# design.net
KiCad netlist of a schematic drawn in Altium Designer
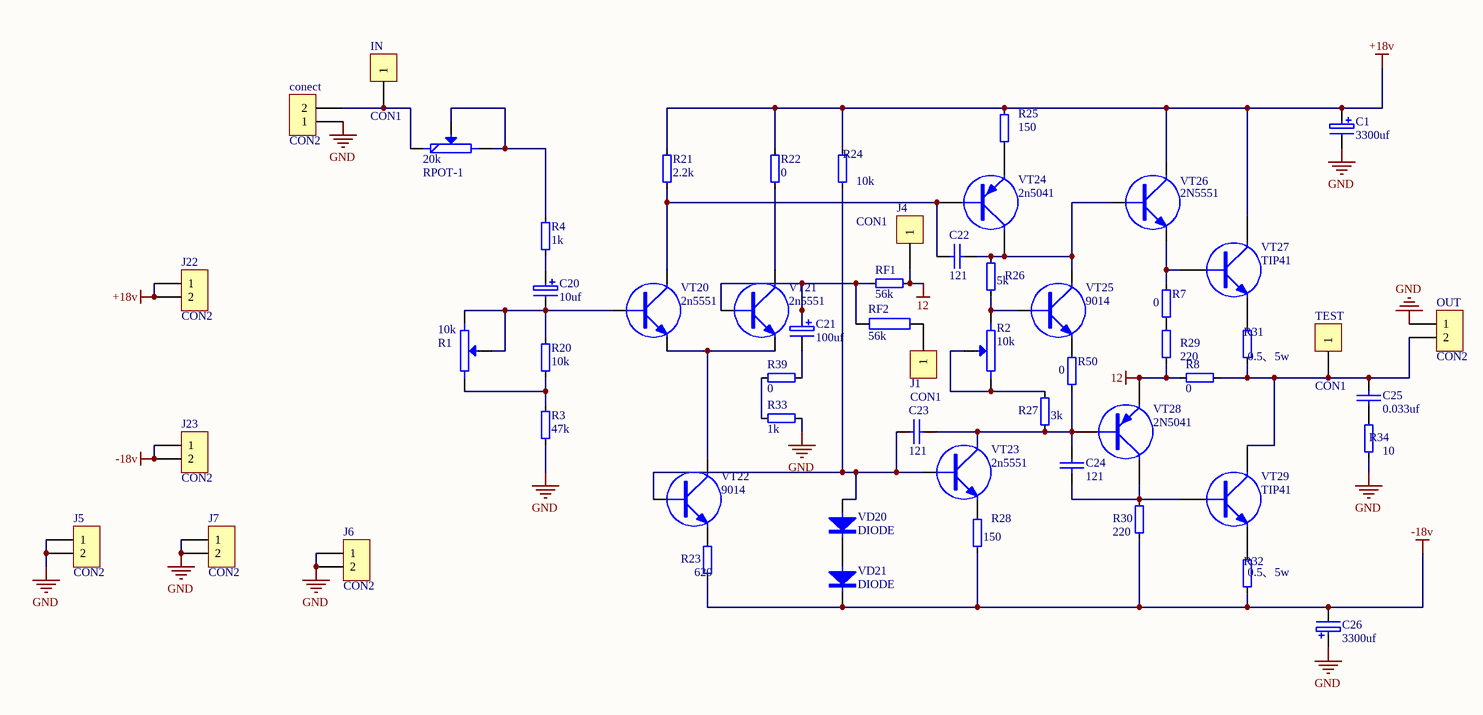
[diagram p0: 分立功放电路原理图.SchDoc]

(export (version "E")
  (design (tool "Eeschema 10.0.6"))
  (components
    (comp (ref "20k")
      (value "RPOT-1")
      (footprint "RVR-A")
      (description "普通电位器")
      (libsource (lib "电阻") (part "RPOT-1"))
    )
    (comp (ref "C1") (value "3300uf") (footprint "C14") (libsource (lib "C电容") (part "CAP3")))
    (comp (ref "C20") (value "10uf") (footprint "CAO1") (libsource (lib "C电容") (part "CAP3")))
    (comp (ref "C21") (value "100uf") (footprint "CAO1") (libsource (lib "C电容") (part "CAP3")))
    (comp (ref "C22") (value "121") (footprint "RAD0.1") (libsource (lib "常用元件库") (part "CAP")))
    (comp (ref "C23") (value "121") (footprint "RAD0.1") (libsource (lib "常用元件库") (part "CAP")))
    (comp (ref "C24") (value "121") (footprint "RAD0.1") (libsource (lib "常用元件库") (part "CAP")))
    (comp (ref "C25") (value "0.033uf") (footprint "RAD0.1") (libsource (lib "常用元件库") (part "CAP")))
    (comp (ref "C26") (value "3300uf") (footprint "C14") (libsource (lib "C电容") (part "CAP3")))
    (comp (ref "conect")
      (value "CON2")
      (footprint "2P-200")
      (description "Connector")
      (libsource (lib "") (part "CON2_1"))
    )
    (comp (ref "IN")
      (value "CON1")
      (footprint "SIP-1")
      (description "Connector")
      (libsource (lib "接口") (part "CON1"))
    )
    (comp (ref "J1")
      (value "CON1")
      (footprint "SIP-1")
      (description "Connector")
      (libsource (lib "") (part "CON1_1"))
    )
    (comp (ref "J4")
      (value "CON1")
      (footprint "SIP-1")
      (description "Connector")
      (libsource (lib "接口") (part "CON1"))
    )
    (comp (ref "J5")
      (value "CON2")
      (footprint "sip-2")
      (description "Connector")
      (libsource (lib "接口") (part "CON2"))
    )
    (comp (ref "J6")
      (value "CON2")
      (footprint "2P-200")
      (description "Connector")
      (libsource (lib "接口") (part "CON2"))
    )
    (comp (ref "J7")
      (value "CON2")
      (footprint "sip-2")
      (description "Connector")
      (libsource (lib "接口") (part "CON2"))
    )
    (comp (ref "J22")
      (value "CON2")
      (footprint "2P-200")
      (description "Connector")
      (libsource (lib "接口") (part "CON2"))
    )
    (comp (ref "J23")
      (value "CON2")
      (footprint "2P-200")
      (description "Connector")
      (libsource (lib "接口") (part "CON2"))
    )
    (comp (ref "OUT")
      (value "CON2")
      (footprint "sip-2")
      (description "Connector")
      (libsource (lib "接口") (part "CON2"))
    )
    (comp (ref "R1")
      (value "10k")
      (footprint "RVR-4")
      (description "Potentiometer")
      (libsource (lib "R电阻") (part "RPOT-1"))
    )
    (comp (ref "R2")
      (value "10k")
      (footprint "RVR-4")
      (description "Potentiometer")
      (libsource (lib "R电阻") (part "RPOT-1"))
    )
    (comp (ref "R3") (value "47k") (footprint "AXIAL0.4") (libsource (lib "电阻") (part "RES")))
    (comp (ref "R4") (value "1k") (footprint "AXIAL0.4") (libsource (lib "电阻") (part "RES")))
    (comp (ref "R7") (value "0") (footprint "AXIAL0.4") (libsource (lib "电阻") (part "RES")))
    (comp (ref "R8") (value "0") (footprint "AXIAL0.4") (libsource (lib "电阻") (part "RES")))
    (comp (ref "R20") (value "10k") (footprint "AXIAL0.4") (libsource (lib "电阻") (part "RES")))
    (comp (ref "R21") (value "2.2k") (footprint "AXIAL0.4") (libsource (lib "电阻") (part "RES")))
    (comp (ref "R22") (value "0") (footprint "AXIAL0.4") (libsource (lib "电阻") (part "RES")))
    (comp (ref "R23") (value "620") (footprint "AXIAL0.4") (libsource (lib "电阻") (part "RES")))
    (comp (ref "R24") (value "10k") (footprint "AXIAL0.4") (libsource (lib "电阻") (part "RES")))
    (comp (ref "R25") (value "150") (footprint "AXIAL0.4") (libsource (lib "电阻") (part "RES")))
    (comp (ref "R26") (value "5k") (footprint "AXIAL0.4") (libsource (lib "电阻") (part "RES")))
    (comp (ref "R27") (value "3k") (footprint "AXIAL0.4") (libsource (lib "电阻") (part "RES")))
    (comp (ref "R28") (value "150") (footprint "AXIAL0.4") (libsource (lib "电阻") (part "RES")))
    (comp (ref "R29") (value "220") (footprint "AXIAL0.4") (libsource (lib "电阻") (part "RES")))
    (comp (ref "R30") (value "220") (footprint "AXIAL0.4") (libsource (lib "电阻") (part "RES")))
    (comp (ref "R31") (value "0.5、5w") (footprint "AXIAL1.0") (libsource (lib "电阻") (part "RES")))
    (comp (ref "R32") (value "0.5、5w") (footprint "AXIAL1.0") (libsource (lib "电阻") (part "RES")))
    (comp (ref "R33") (value "1k") (footprint "AXIAL0.4") (libsource (lib "电阻") (part "RES")))
    (comp (ref "R34") (value "10") (footprint "AXIAL0.4") (libsource (lib "电阻") (part "RES")))
    (comp (ref "R39") (value "0") (footprint "AXIAL0.4") (libsource (lib "电阻") (part "RES")))
    (comp (ref "R50") (value "0") (footprint "AXIAL0.4") (libsource (lib "电阻") (part "RES")))
    (comp (ref "RF1") (value "56k") (footprint "AXIAL0.4") (libsource (lib "电阻") (part "RES")))
    (comp (ref "RF2")
      (value "56k")
      (footprint "AXIAL0.4")
      (description "电阻")
      (libsource (lib "") (part "RES_1"))
    )
    (comp (ref "TEST")
      (value "CON1")
      (footprint "SIP-1")
      (description "Connector")
      (libsource (lib "接口") (part "CON1"))
    )
    (comp (ref "VD20") (value "DIODE") (footprint "DIODE0.4") (libsource (lib "Diode二极管") (part "DIODE")))
    (comp (ref "VD21") (value "DIODE") (footprint "DIODE0.4") (libsource (lib "Diode二极管") (part "DIODE")))
    (comp (ref "VT20") (value "2n5551") (footprint "TO126V") (libsource (lib "V三极管") (part "9014")))
    (comp (ref "VT21") (value "2n5551") (footprint "TO126V") (libsource (lib "V三极管") (part "9014")))
    (comp (ref "VT22") (value "9014") (footprint "TO126V") (libsource (lib "V三极管") (part "9014")))
    (comp (ref "VT23") (value "2n5551") (footprint "TO126V") (libsource (lib "V三极管") (part "9014")))
    (comp (ref "VT24") (value "2n5041") (footprint "TO126V") (libsource (lib "V三极管") (part "9012")))
    (comp (ref "VT25") (value "9014") (footprint "TO126V") (libsource (lib "V三极管") (part "9014")))
    (comp (ref "VT26") (value "2N5551") (footprint "TO126V") (libsource (lib "V三极管") (part "9014")))
    (comp (ref "VT27")
      (value "TIP41")
      (footprint "TO-220")
      (description "NPN PLASTIC POWER TRANSISTORS")
      (libsource (lib "V三极管") (part "TIP41"))
    )
    (comp (ref "VT28") (value "2N5041") (footprint "TO126V") (libsource (lib "V三极管") (part "9012")))
    (comp (ref "VT29")
      (value "TIP41")
      (footprint "TO-220")
      (description "NPN PLASTIC POWER TRANSISTORS")
      (libsource (lib "V三极管") (part "TIP41"))
    )
  )
  (nets
    (net (code "1") (name "+18v") (class "Default")
      (node (ref "C1") (pin "1") (pintype "passive"))
      (node (ref "J22") (pin "1") (pinfunction "1_1") (pintype "passive"))
      (node (ref "J22") (pin "2") (pinfunction "2_2") (pintype "passive"))
      (node (ref "R21") (pin "1") (pinfunction "1_1") (pintype "passive"))
      (node (ref "R22") (pin "1") (pinfunction "1_1") (pintype "passive"))
      (node (ref "R24") (pin "1") (pinfunction "1_1") (pintype "passive"))
      (node (ref "R25") (pin "1") (pinfunction "1_1") (pintype "passive"))
      (node (ref "VT26") (pin "3") (pinfunction "C_3") (pintype "passive"))
      (node (ref "VT27") (pin "2") (pinfunction "C_2") (pintype "passive"))
    )
    (net (code "2") (name "-18v") (class "Default")
      (node (ref "C26") (pin "2") (pintype "passive"))
      (node (ref "J23") (pin "1") (pinfunction "1_1") (pintype "passive"))
      (node (ref "J23") (pin "2") (pinfunction "2_2") (pintype "passive"))
      (node (ref "R23") (pin "2") (pinfunction "2_2") (pintype "passive"))
      (node (ref "R28") (pin "2") (pinfunction "2_2") (pintype "passive"))
      (node (ref "R30") (pin "2") (pinfunction "2_2") (pintype "passive"))
      (node (ref "R32") (pin "2") (pinfunction "2_2") (pintype "passive"))
      (node (ref "VD21") (pin "2") (pinfunction "2_2") (pintype "passive"))
    )
    (net (code "3") (name "12") (class "Default")
      (node (ref "J4") (pin "1") (pinfunction "1_1") (pintype "passive"))
      (node (ref "R29") (pin "2") (pinfunction "2_2") (pintype "passive"))
      (node (ref "R8") (pin "1") (pinfunction "1_1") (pintype "passive"))
      (node (ref "RF1") (pin "2") (pinfunction "2_2") (pintype "passive"))
      (node (ref "VT28") (pin "1") (pinfunction "E_1") (pintype "passive"))
    )
    (net (code "4") (name "GND") (class "Default")
      (node (ref "C1") (pin "2") (pintype "passive"))
      (node (ref "C26") (pin "1") (pintype "passive"))
      (node (ref "J5") (pin "1") (pinfunction "1_1") (pintype "passive"))
      (node (ref "J5") (pin "2") (pinfunction "2_2") (pintype "passive"))
      (node (ref "J6") (pin "1") (pinfunction "1_1") (pintype "passive"))
      (node (ref "J6") (pin "2") (pinfunction "2_2") (pintype "passive"))
      (node (ref "J7") (pin "1") (pinfunction "1_1") (pintype "passive"))
      (node (ref "J7") (pin "2") (pinfunction "2_2") (pintype "passive"))
      (node (ref "OUT") (pin "1") (pinfunction "1_1") (pintype "passive"))
      (node (ref "R3") (pin "2") (pinfunction "2_2") (pintype "passive"))
      (node (ref "R33") (pin "2") (pinfunction "2_2") (pintype "passive"))
      (node (ref "R34") (pin "2") (pinfunction "2_2") (pintype "passive"))
      (node (ref "conect") (pin "1") (pinfunction "1_1") (pintype "passive"))
    )
    (net (code "5") (name "Net-(20k-M)") (class "Default")
      (node (ref "20k") (pin "2") (pinfunction "M_2") (pintype "passive"))
      (node (ref "20k") (pin "3") (pinfunction "3_3") (pintype "passive"))
      (node (ref "R4") (pin "1") (pinfunction "1_1") (pintype "passive"))
    )
    (net (code "6") (name "Net-(20k-Pad1)") (class "Default")
      (node (ref "20k") (pin "1") (pinfunction "1_1") (pintype "passive"))
      (node (ref "IN") (pin "1") (pinfunction "1_1") (pintype "passive"))
      (node (ref "conect") (pin "2") (pinfunction "2_2") (pintype "passive"))
    )
    (net (code "7") (name "Net-(C20-Pad1)") (class "Default")
      (node (ref "C20") (pin "1") (pintype "passive"))
      (node (ref "R4") (pin "2") (pinfunction "2_2") (pintype "passive"))
    )
    (net (code "8") (name "Net-(C21-Pad2)") (class "Default")
      (node (ref "C21") (pin "2") (pintype "passive"))
      (node (ref "R39") (pin "2") (pinfunction "2_2") (pintype "passive"))
    )
    (net (code "9") (name "Net-(C25-Pad1)") (class "Default")
      (node (ref "C25") (pin "1") (pinfunction "1_1") (pintype "passive"))
      (node (ref "R34") (pin "1") (pinfunction "1_1") (pintype "passive"))
    )
    (net (code "10") (name "Net-(J1-Pad1)") (class "Default")
      (node (ref "J1") (pin "1") (pinfunction "1_1") (pintype "passive"))
      (node (ref "RF2") (pin "2") (pinfunction "2_2") (pintype "passive"))
    )
    (net (code "11") (name "Net-(R1-Pad3)") (class "Default")
      (node (ref "R1") (pin "3") (pinfunction "3_3") (pintype "passive"))
      (node (ref "R20") (pin "2") (pinfunction "2_2") (pintype "passive"))
      (node (ref "R3") (pin "1") (pinfunction "1_1") (pintype "passive"))
    )
    (net (code "12") (name "Net-(R1-W)") (class "Default")
      (node (ref "C20") (pin "2") (pintype "passive"))
      (node (ref "R1") (pin "1") (pinfunction "1_1") (pintype "passive"))
      (node (ref "R1") (pin "2") (pinfunction "W_2") (pintype "passive"))
      (node (ref "R20") (pin "1") (pinfunction "1_1") (pintype "passive"))
      (node (ref "VT20") (pin "2") (pinfunction "B_2") (pintype "passive"))
    )
    (net (code "13") (name "Net-(R2-W)") (class "Default")
      (node (ref "R2") (pin "1") (pinfunction "1_1") (pintype "passive"))
      (node (ref "R2") (pin "2") (pinfunction "W_2") (pintype "passive"))
      (node (ref "R27") (pin "1") (pinfunction "1_1") (pintype "passive"))
    )
    (net (code "14") (name "Net-(R29-Pad1)") (class "Default")
      (node (ref "R29") (pin "1") (pinfunction "1_1") (pintype "passive"))
      (node (ref "R7") (pin "2") (pinfunction "2_2") (pintype "passive"))
    )
    (net (code "15") (name "Net-(R33-Pad1)") (class "Default")
      (node (ref "R33") (pin "1") (pinfunction "1_1") (pintype "passive"))
      (node (ref "R39") (pin "1") (pinfunction "1_1") (pintype "passive"))
    )
    (net (code "16") (name "Net-(VD20-Pad2)") (class "Default")
      (node (ref "VD20") (pin "2") (pinfunction "2_2") (pintype "passive"))
      (node (ref "VD21") (pin "1") (pinfunction "1_1") (pintype "passive"))
    )
    (net (code "17") (name "Net-(VT20-C)") (class "Default")
      (node (ref "C22") (pin "1") (pinfunction "1_1") (pintype "passive"))
      (node (ref "R21") (pin "2") (pinfunction "2_2") (pintype "passive"))
      (node (ref "VT20") (pin "3") (pinfunction "C_3") (pintype "passive"))
      (node (ref "VT24") (pin "2") (pinfunction "B_2") (pintype "passive"))
    )
    (net (code "18") (name "Net-(VT20-E)") (class "Default")
      (node (ref "VT20") (pin "1") (pinfunction "E_1") (pintype "passive"))
      (node (ref "VT21") (pin "1") (pinfunction "E_1") (pintype "passive"))
      (node (ref "VT22") (pin "3") (pinfunction "C_3") (pintype "passive"))
    )
    (net (code "19") (name "Net-(VT21-B)") (class "Default")
      (node (ref "C21") (pin "1") (pintype "passive"))
      (node (ref "RF1") (pin "1") (pinfunction "1_1") (pintype "passive"))
      (node (ref "RF2") (pin "1") (pinfunction "1_1") (pintype "passive"))
      (node (ref "VT21") (pin "2") (pinfunction "B_2") (pintype "passive"))
    )
    (net (code "20") (name "Net-(VT21-C)") (class "Default")
      (node (ref "R22") (pin "2") (pinfunction "2_2") (pintype "passive"))
      (node (ref "VT21") (pin "3") (pinfunction "C_3") (pintype "passive"))
    )
    (net (code "21") (name "Net-(VT22-B)") (class "Default")
      (node (ref "C23") (pin "1") (pinfunction "1_1") (pintype "passive"))
      (node (ref "R24") (pin "2") (pinfunction "2_2") (pintype "passive"))
      (node (ref "VD20") (pin "1") (pinfunction "1_1") (pintype "passive"))
      (node (ref "VT22") (pin "2") (pinfunction "B_2") (pintype "passive"))
      (node (ref "VT23") (pin "2") (pinfunction "B_2") (pintype "passive"))
    )
    (net (code "22") (name "Net-(VT22-E)") (class "Default")
      (node (ref "R23") (pin "1") (pinfunction "1_1") (pintype "passive"))
      (node (ref "VT22") (pin "1") (pinfunction "E_1") (pintype "passive"))
    )
    (net (code "23") (name "Net-(VT23-C)") (class "Default")
      (node (ref "C23") (pin "2") (pinfunction "2_2") (pintype "passive"))
      (node (ref "C24") (pin "2") (pinfunction "2_2") (pintype "passive"))
      (node (ref "R27") (pin "2") (pinfunction "2_2") (pintype "passive"))
      (node (ref "R50") (pin "2") (pinfunction "2_2") (pintype "passive"))
      (node (ref "VT23") (pin "3") (pinfunction "C_3") (pintype "passive"))
      (node (ref "VT28") (pin "2") (pinfunction "B_2") (pintype "passive"))
    )
    (net (code "24") (name "Net-(VT23-E)") (class "Default")
      (node (ref "R28") (pin "1") (pinfunction "1_1") (pintype "passive"))
      (node (ref "VT23") (pin "1") (pinfunction "E_1") (pintype "passive"))
    )
    (net (code "25") (name "Net-(VT24-C)") (class "Default")
      (node (ref "C22") (pin "2") (pinfunction "2_2") (pintype "passive"))
      (node (ref "R26") (pin "1") (pinfunction "1_1") (pintype "passive"))
      (node (ref "VT24") (pin "3") (pinfunction "C_3") (pintype "passive"))
      (node (ref "VT25") (pin "3") (pinfunction "C_3") (pintype "passive"))
      (node (ref "VT26") (pin "2") (pinfunction "B_2") (pintype "passive"))
    )
    (net (code "26") (name "Net-(VT24-E)") (class "Default")
      (node (ref "R25") (pin "2") (pinfunction "2_2") (pintype "passive"))
      (node (ref "VT24") (pin "1") (pinfunction "E_1") (pintype "passive"))
    )
    (net (code "27") (name "Net-(VT25-B)") (class "Default")
      (node (ref "R2") (pin "3") (pinfunction "3_3") (pintype "passive"))
      (node (ref "R26") (pin "2") (pinfunction "2_2") (pintype "passive"))
      (node (ref "VT25") (pin "2") (pinfunction "B_2") (pintype "passive"))
    )
    (net (code "28") (name "Net-(VT25-E)") (class "Default")
      (node (ref "R50") (pin "1") (pinfunction "1_1") (pintype "passive"))
      (node (ref "VT25") (pin "1") (pinfunction "E_1") (pintype "passive"))
    )
    (net (code "29") (name "Net-(VT26-E)") (class "Default")
      (node (ref "R7") (pin "1") (pinfunction "1_1") (pintype "passive"))
      (node (ref "VT26") (pin "1") (pinfunction "E_1") (pintype "passive"))
      (node (ref "VT27") (pin "1") (pinfunction "B_1") (pintype "passive"))
    )
    (net (code "30") (name "Net-(VT27-E)") (class "Default")
      (node (ref "R31") (pin "1") (pinfunction "1_1") (pintype "passive"))
      (node (ref "VT27") (pin "3") (pinfunction "E_3") (pintype "passive"))
    )
    (net (code "31") (name "Net-(VT28-C)") (class "Default")
      (node (ref "C24") (pin "1") (pinfunction "1_1") (pintype "passive"))
      (node (ref "R30") (pin "1") (pinfunction "1_1") (pintype "passive"))
      (node (ref "VT28") (pin "3") (pinfunction "C_3") (pintype "passive"))
      (node (ref "VT29") (pin "1") (pinfunction "B_1") (pintype "passive"))
    )
    (net (code "32") (name "Net-(VT29-C)") (class "Default")
      (node (ref "C25") (pin "2") (pinfunction "2_2") (pintype "passive"))
      (node (ref "OUT") (pin "2") (pinfunction "2_2") (pintype "passive"))
      (node (ref "R31") (pin "2") (pinfunction "2_2") (pintype "passive"))
      (node (ref "R8") (pin "2") (pinfunction "2_2") (pintype "passive"))
      (node (ref "TEST") (pin "1") (pinfunction "1_1") (pintype "passive"))
      (node (ref "VT29") (pin "2") (pinfunction "C_2") (pintype "passive"))
    )
    (net (code "33") (name "Net-(VT29-E)") (class "Default")
      (node (ref "R32") (pin "1") (pinfunction "1_1") (pintype "passive"))
      (node (ref "VT29") (pin "3") (pinfunction "E_3") (pintype "passive"))
    )
  )
)
